# controller2.net
KiCad netlist of a schematic drawn in EAGLE
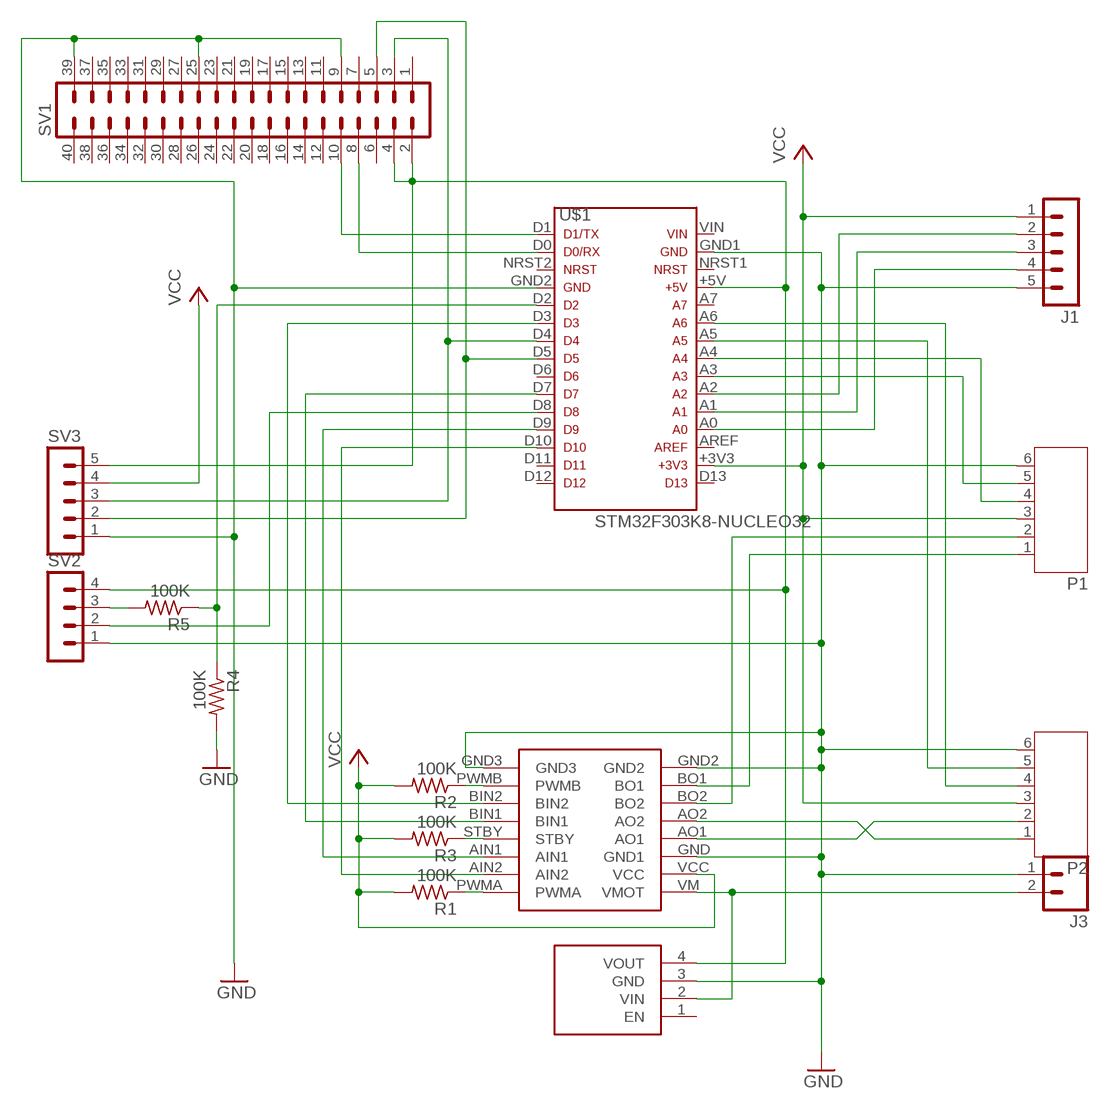
[diagram p0: schematic, sheet 1]

(export (version "E")
  (design (tool "Eeschema 10.0.6"))
  (components
    (comp (ref "J1")
      (value "MA05-1")
      (footprint "eagle-import:MA05-1")
      (libsource (lib "eagle-import") (part "MA05-1"))
    )
    (comp (ref "J3")
      (value "M02JST-PTH-VERT")
      (footprint "eagle-import:JST-2-PTH-VERT")
      (libsource (lib "eagle-import") (part "M02JST-PTH-VERT"))
    )
    (comp (ref "P1")
      (value "JST-PH6")
      (footprint "eagle-import:JST-PH6")
      (libsource (lib "eagle-import") (part "JST-PH6"))
    )
    (comp (ref "P2")
      (value "JST-PH6")
      (footprint "eagle-import:JST-PH6")
      (libsource (lib "eagle-import") (part "JST-PH6"))
    )
    (comp (ref "R1")
      (value "100K")
      (footprint "eagle-import:M0805")
      (libsource (lib "eagle-import") (part "R-US_M0805"))
    )
    (comp (ref "R2")
      (value "100K")
      (footprint "eagle-import:M0805")
      (libsource (lib "eagle-import") (part "R-US_M0805"))
    )
    (comp (ref "R3")
      (value "100K")
      (footprint "eagle-import:M0805")
      (libsource (lib "eagle-import") (part "R-US_M0805"))
    )
    (comp (ref "R4")
      (value "100K")
      (footprint "eagle-import:M0805")
      (libsource (lib "eagle-import") (part "R-US_M0805"))
    )
    (comp (ref "R5")
      (value "100K")
      (footprint "eagle-import:M0805")
      (libsource (lib "eagle-import") (part "R-US_M0805"))
    )
    (comp (ref "SV1")
      (value "MA20-2")
      (footprint "eagle-import:MA20-2")
      (libsource (lib "eagle-import") (part "MA20-2"))
    )
    (comp (ref "SV2")
      (value "MA04-1")
      (footprint "eagle-import:MA04-1")
      (libsource (lib "eagle-import") (part "MA04-1"))
    )
    (comp (ref "SV3")
      (value "MA05-1")
      (footprint "eagle-import:MA05-1")
      (libsource (lib "eagle-import") (part "MA05-1"))
    )
    (comp (ref "U$1")
      (value "STM32F303K8-NUCLEO32")
      (footprint "eagle-import:NUCLEO32")
      (libsource (lib "eagle-import") (part "STM32F303K8-NUCLEO32"))
    )
    (comp (ref "U$2")
      (value "TB6612FNG-CARRIER/SPARKFUN")
      (footprint "eagle-import:TB6612FNG-BRKOUT_SPARKFUN")
      (libsource (lib "eagle-import") (part "TB6612FNG-CARRIER/SPARKFUN"))
    )
    (comp (ref "U$3")
      (value "S7V8A")
      (footprint "eagle-import:S7V8")
      (libsource (lib "eagle-import") (part "S7V8A"))
    )
  )
  (nets
    (net (code "1") (name "GND") (class "Default")
      (node (ref "J1") (pin "5") (pinfunction "5_5") (pintype "passive"))
      (node (ref "J3") (pin "1") (pinfunction "1_1") (pintype "passive"))
      (node (ref "P1") (pin "6") (pinfunction "6_6") (pintype "passive"))
      (node (ref "P2") (pin "6") (pinfunction "6_6") (pintype "passive"))
      (node (ref "R4") (pin "2") (pinfunction "2_2") (pintype "passive"))
      (node (ref "SV1") (pin "25") (pinfunction "25_25") (pintype "passive"))
      (node (ref "SV1") (pin "39") (pinfunction "39_39") (pintype "passive"))
      (node (ref "SV1") (pin "9") (pinfunction "9_9") (pintype "passive"))
      (node (ref "SV2") (pin "1") (pinfunction "1_1") (pintype "passive"))
      (node (ref "SV3") (pin "1") (pinfunction "1_1") (pintype "passive"))
      (node (ref "U$1") (pin "GND1") (pinfunction "GND1_GND1") (pintype "passive"))
      (node (ref "U$1") (pin "GND2") (pinfunction "GND2_GND2") (pintype "passive"))
      (node (ref "U$2") (pin "GND") (pinfunction "GND1_GND") (pintype "bidirectional"))
      (node (ref "U$2") (pin "GND2") (pinfunction "GND2_GND2") (pintype "bidirectional"))
      (node (ref "U$2") (pin "GND3") (pinfunction "GND3_GND3") (pintype "bidirectional"))
      (node (ref "U$3") (pin "3") (pinfunction "GND_3") (pintype "bidirectional"))
    )
    (net (code "2") (name "Net-(J1-Pad2)") (class "Default")
      (node (ref "J1") (pin "2") (pinfunction "2_2") (pintype "passive"))
      (node (ref "U$1") (pin "A2") (pinfunction "A2_A2") (pintype "passive"))
    )
    (net (code "3") (name "Net-(J1-Pad3)") (class "Default")
      (node (ref "J1") (pin "3") (pinfunction "3_3") (pintype "passive"))
      (node (ref "U$1") (pin "A1") (pinfunction "A1_A1") (pintype "passive"))
    )
    (net (code "4") (name "Net-(J1-Pad4)") (class "Default")
      (node (ref "J1") (pin "4") (pinfunction "4_4") (pintype "passive"))
      (node (ref "U$1") (pin "A0") (pinfunction "A0_A0") (pintype "passive"))
    )
    (net (code "5") (name "Net-(P1-Pad1)") (class "Default")
      (node (ref "P1") (pin "1") (pinfunction "1_1") (pintype "passive"))
      (node (ref "U$2") (pin "BO1") (pinfunction "BO1_BO1") (pintype "bidirectional"))
    )
    (net (code "6") (name "Net-(P1-Pad2)") (class "Default")
      (node (ref "P1") (pin "2") (pinfunction "2_2") (pintype "passive"))
      (node (ref "U$2") (pin "BO2") (pinfunction "BO2_BO2") (pintype "bidirectional"))
    )
    (net (code "7") (name "Net-(P1-Pad4)") (class "Default")
      (node (ref "P1") (pin "4") (pinfunction "4_4") (pintype "passive"))
      (node (ref "U$1") (pin "A4") (pinfunction "A4_A4") (pintype "passive"))
    )
    (net (code "8") (name "Net-(P1-Pad5)") (class "Default")
      (node (ref "P1") (pin "5") (pinfunction "5_5") (pintype "passive"))
      (node (ref "U$1") (pin "A3") (pinfunction "A3_A3") (pintype "passive"))
    )
    (net (code "9") (name "Net-(P2-Pad1)") (class "Default")
      (node (ref "P2") (pin "1") (pinfunction "1_1") (pintype "passive"))
      (node (ref "U$2") (pin "AO2") (pinfunction "AO2_AO2") (pintype "bidirectional"))
    )
    (net (code "10") (name "Net-(P2-Pad2)") (class "Default")
      (node (ref "P2") (pin "2") (pinfunction "2_2") (pintype "passive"))
      (node (ref "U$2") (pin "AO1") (pinfunction "AO1_AO1") (pintype "bidirectional"))
    )
    (net (code "11") (name "Net-(P2-Pad4)") (class "Default")
      (node (ref "P2") (pin "4") (pinfunction "4_4") (pintype "passive"))
      (node (ref "U$1") (pin "A6") (pinfunction "A6_A6") (pintype "passive"))
    )
    (net (code "12") (name "Net-(P2-Pad5)") (class "Default")
      (node (ref "P2") (pin "5") (pinfunction "5_5") (pintype "passive"))
      (node (ref "U$1") (pin "A5") (pinfunction "A5_A5") (pintype "passive"))
    )
    (net (code "13") (name "Net-(R1-Pad1)") (class "Default")
      (node (ref "R1") (pin "1") (pinfunction "1_1") (pintype "passive"))
      (node (ref "U$2") (pin "PWMA") (pinfunction "PWMA_PWMA") (pintype "bidirectional"))
    )
    (net (code "14") (name "Net-(R2-Pad1)") (class "Default")
      (node (ref "R2") (pin "1") (pinfunction "1_1") (pintype "passive"))
      (node (ref "U$2") (pin "PWMB") (pinfunction "PWMB_PWMB") (pintype "bidirectional"))
    )
    (net (code "15") (name "Net-(R3-Pad1)") (class "Default")
      (node (ref "R3") (pin "1") (pinfunction "1_1") (pintype "passive"))
      (node (ref "U$2") (pin "STBY") (pinfunction "STBY_STBY") (pintype "bidirectional"))
    )
    (net (code "16") (name "Net-(R4-Pad1)") (class "Default")
      (node (ref "R4") (pin "1") (pinfunction "1_1") (pintype "passive"))
      (node (ref "R5") (pin "1") (pinfunction "1_1") (pintype "passive"))
      (node (ref "U$1") (pin "D2") (pinfunction "D2_D2") (pintype "passive"))
    )
    (net (code "17") (name "Net-(R5-Pad2)") (class "Default")
      (node (ref "R5") (pin "2") (pinfunction "2_2") (pintype "passive"))
      (node (ref "SV2") (pin "3") (pinfunction "3_3") (pintype "passive"))
    )
    (net (code "18") (name "Net-(SV1-Pad3)") (class "Default")
      (node (ref "SV1") (pin "3") (pinfunction "3_3") (pintype "passive"))
      (node (ref "SV3") (pin "3") (pinfunction "3_3") (pintype "passive"))
      (node (ref "U$1") (pin "D4") (pinfunction "D4_D4") (pintype "passive"))
    )
    (net (code "19") (name "Net-(SV1-Pad5)") (class "Default")
      (node (ref "SV1") (pin "5") (pinfunction "5_5") (pintype "passive"))
      (node (ref "SV3") (pin "2") (pinfunction "2_2") (pintype "passive"))
      (node (ref "U$1") (pin "D5") (pinfunction "D5_D5") (pintype "passive"))
    )
    (net (code "20") (name "Net-(SV1-Pad8)") (class "Default")
      (node (ref "SV1") (pin "8") (pinfunction "8_8") (pintype "passive"))
      (node (ref "U$1") (pin "D0") (pinfunction "D0_D0") (pintype "passive"))
    )
    (net (code "21") (name "Net-(SV1-Pad10)") (class "Default")
      (node (ref "SV1") (pin "10") (pinfunction "10_10") (pintype "passive"))
      (node (ref "U$1") (pin "D1") (pinfunction "D1_D1") (pintype "passive"))
    )
    (net (code "22") (name "Net-(SV2-Pad2)") (class "Default")
      (node (ref "SV2") (pin "2") (pinfunction "2_2") (pintype "passive"))
      (node (ref "U$1") (pin "D8") (pinfunction "D8_D8") (pintype "passive"))
    )
    (net (code "23") (name "Net-(U$1-PadD3)") (class "Default")
      (node (ref "U$1") (pin "D3") (pinfunction "D3_D3") (pintype "passive"))
      (node (ref "U$2") (pin "BIN2") (pinfunction "BIN2_BIN2") (pintype "bidirectional"))
    )
    (net (code "24") (name "Net-(U$1-PadD7)") (class "Default")
      (node (ref "U$1") (pin "D7") (pinfunction "D7_D7") (pintype "passive"))
      (node (ref "U$2") (pin "BIN1") (pinfunction "BIN1_BIN1") (pintype "bidirectional"))
    )
    (net (code "25") (name "Net-(U$1-PadD9)") (class "Default")
      (node (ref "U$1") (pin "D9") (pinfunction "D9_D9") (pintype "passive"))
      (node (ref "U$2") (pin "AIN1") (pinfunction "AIN1_AIN1") (pintype "bidirectional"))
    )
    (net (code "26") (name "Net-(U$1-PadD10)") (class "Default")
      (node (ref "U$1") (pin "D10") (pinfunction "D10_D10") (pintype "passive"))
      (node (ref "U$2") (pin "AIN2") (pinfunction "AIN2_AIN2") (pintype "bidirectional"))
    )
    (net (code "27") (name "Net-(U$2-VMOT)") (class "Default")
      (node (ref "J3") (pin "2") (pinfunction "2_2") (pintype "passive"))
      (node (ref "U$2") (pin "VM") (pinfunction "VMOT_VM") (pintype "bidirectional"))
      (node (ref "U$3") (pin "2") (pinfunction "VIN_2") (pintype "bidirectional"))
    )
    (net (code "28") (name "Net-(U$3-VOUT)") (class "Default")
      (node (ref "SV1") (pin "2") (pinfunction "2_2") (pintype "passive"))
      (node (ref "SV1") (pin "4") (pinfunction "4_4") (pintype "passive"))
      (node (ref "SV2") (pin "4") (pinfunction "4_4") (pintype "passive"))
      (node (ref "SV3") (pin "5") (pinfunction "5_5") (pintype "passive"))
      (node (ref "U$1") (pin "+5V") (pinfunction "+5V_+5V") (pintype "passive"))
      (node (ref "U$3") (pin "4") (pinfunction "VOUT_4") (pintype "bidirectional"))
    )
    (net (code "29") (name "VCC") (class "Default")
      (node (ref "J1") (pin "1") (pinfunction "1_1") (pintype "passive"))
      (node (ref "P1") (pin "3") (pinfunction "3_3") (pintype "passive"))
      (node (ref "P2") (pin "3") (pinfunction "3_3") (pintype "passive"))
      (node (ref "R1") (pin "2") (pinfunction "2_2") (pintype "passive"))
      (node (ref "R2") (pin "2") (pinfunction "2_2") (pintype "passive"))
      (node (ref "R3") (pin "2") (pinfunction "2_2") (pintype "passive"))
      (node (ref "SV3") (pin "4") (pinfunction "4_4") (pintype "passive"))
      (node (ref "U$1") (pin "+3V3") (pinfunction "+3V3_+3V3") (pintype "passive"))
      (node (ref "U$2") (pin "VCC") (pinfunction "VCC_VCC") (pintype "bidirectional"))
    )
    (net (code "30") (name "unconnected-(SV1-Pad1)") (class "Default")
      (node (ref "SV1") (pin "1") (pinfunction "1_1") (pintype "passive"))
    )
    (net (code "31") (name "unconnected-(SV1-Pad6)") (class "Default")
      (node (ref "SV1") (pin "6") (pinfunction "6_6") (pintype "passive"))
    )
    (net (code "32") (name "unconnected-(SV1-Pad7)") (class "Default")
      (node (ref "SV1") (pin "7") (pinfunction "7_7") (pintype "passive"))
    )
    (net (code "33") (name "unconnected-(SV1-Pad11)") (class "Default")
      (node (ref "SV1") (pin "11") (pinfunction "11_11") (pintype "passive"))
    )
    (net (code "34") (name "unconnected-(SV1-Pad12)") (class "Default")
      (node (ref "SV1") (pin "12") (pinfunction "12_12") (pintype "passive"))
    )
    (net (code "35") (name "unconnected-(SV1-Pad13)") (class "Default")
      (node (ref "SV1") (pin "13") (pinfunction "13_13") (pintype "passive"))
    )
    (net (code "36") (name "unconnected-(SV1-Pad14)") (class "Default")
      (node (ref "SV1") (pin "14") (pinfunction "14_14") (pintype "passive"))
    )
    (net (code "37") (name "unconnected-(SV1-Pad15)") (class "Default")
      (node (ref "SV1") (pin "15") (pinfunction "15_15") (pintype "passive"))
    )
    (net (code "38") (name "unconnected-(SV1-Pad16)") (class "Default")
      (node (ref "SV1") (pin "16") (pinfunction "16_16") (pintype "passive"))
    )
    (net (code "39") (name "unconnected-(SV1-Pad17)") (class "Default")
      (node (ref "SV1") (pin "17") (pinfunction "17_17") (pintype "passive"))
    )
    (net (code "40") (name "unconnected-(SV1-Pad18)") (class "Default")
      (node (ref "SV1") (pin "18") (pinfunction "18_18") (pintype "passive"))
    )
    (net (code "41") (name "unconnected-(SV1-Pad19)") (class "Default")
      (node (ref "SV1") (pin "19") (pinfunction "19_19") (pintype "passive"))
    )
    (net (code "42") (name "unconnected-(SV1-Pad20)") (class "Default")
      (node (ref "SV1") (pin "20") (pinfunction "20_20") (pintype "passive"))
    )
    (net (code "43") (name "unconnected-(SV1-Pad21)") (class "Default")
      (node (ref "SV1") (pin "21") (pinfunction "21_21") (pintype "passive"))
    )
    (net (code "44") (name "unconnected-(SV1-Pad22)") (class "Default")
      (node (ref "SV1") (pin "22") (pinfunction "22_22") (pintype "passive"))
    )
    (net (code "45") (name "unconnected-(SV1-Pad23)") (class "Default")
      (node (ref "SV1") (pin "23") (pinfunction "23_23") (pintype "passive"))
    )
    (net (code "46") (name "unconnected-(SV1-Pad24)") (class "Default")
      (node (ref "SV1") (pin "24") (pinfunction "24_24") (pintype "passive"))
    )
    (net (code "47") (name "unconnected-(SV1-Pad26)") (class "Default")
      (node (ref "SV1") (pin "26") (pinfunction "26_26") (pintype "passive"))
    )
    (net (code "48") (name "unconnected-(SV1-Pad27)") (class "Default")
      (node (ref "SV1") (pin "27") (pinfunction "27_27") (pintype "passive"))
    )
    (net (code "49") (name "unconnected-(SV1-Pad28)") (class "Default")
      (node (ref "SV1") (pin "28") (pinfunction "28_28") (pintype "passive"))
    )
    (net (code "50") (name "unconnected-(SV1-Pad29)") (class "Default")
      (node (ref "SV1") (pin "29") (pinfunction "29_29") (pintype "passive"))
    )
    (net (code "51") (name "unconnected-(SV1-Pad30)") (class "Default")
      (node (ref "SV1") (pin "30") (pinfunction "30_30") (pintype "passive"))
    )
    (net (code "52") (name "unconnected-(SV1-Pad31)") (class "Default")
      (node (ref "SV1") (pin "31") (pinfunction "31_31") (pintype "passive"))
    )
    (net (code "53") (name "unconnected-(SV1-Pad32)") (class "Default")
      (node (ref "SV1") (pin "32") (pinfunction "32_32") (pintype "passive"))
    )
    (net (code "54") (name "unconnected-(SV1-Pad33)") (class "Default")
      (node (ref "SV1") (pin "33") (pinfunction "33_33") (pintype "passive"))
    )
    (net (code "55") (name "unconnected-(SV1-Pad34)") (class "Default")
      (node (ref "SV1") (pin "34") (pinfunction "34_34") (pintype "passive"))
    )
    (net (code "56") (name "unconnected-(SV1-Pad35)") (class "Default")
      (node (ref "SV1") (pin "35") (pinfunction "35_35") (pintype "passive"))
    )
    (net (code "57") (name "unconnected-(SV1-Pad36)") (class "Default")
      (node (ref "SV1") (pin "36") (pinfunction "36_36") (pintype "passive"))
    )
    (net (code "58") (name "unconnected-(SV1-Pad37)") (class "Default")
      (node (ref "SV1") (pin "37") (pinfunction "37_37") (pintype "passive"))
    )
    (net (code "59") (name "unconnected-(SV1-Pad38)") (class "Default")
      (node (ref "SV1") (pin "38") (pinfunction "38_38") (pintype "passive"))
    )
    (net (code "60") (name "unconnected-(SV1-Pad40)") (class "Default")
      (node (ref "SV1") (pin "40") (pinfunction "40_40") (pintype "passive"))
    )
    (net (code "61") (name "unconnected-(U$1-PadA7)") (class "Default")
      (node (ref "U$1") (pin "A7") (pinfunction "A7_A7") (pintype "passive"))
    )
    (net (code "62") (name "unconnected-(U$1-PadAREF)") (class "Default")
      (node (ref "U$1") (pin "AREF") (pinfunction "AREF_AREF") (pintype "passive"))
    )
    (net (code "63") (name "unconnected-(U$1-PadD6)") (class "Default")
      (node (ref "U$1") (pin "D6") (pinfunction "D6_D6") (pintype "passive"))
    )
    (net (code "64") (name "unconnected-(U$1-PadD11)") (class "Default")
      (node (ref "U$1") (pin "D11") (pinfunction "D11_D11") (pintype "passive"))
    )
    (net (code "65") (name "unconnected-(U$1-PadD12)") (class "Default")
      (node (ref "U$1") (pin "D12") (pinfunction "D12_D12") (pintype "passive"))
    )
    (net (code "66") (name "unconnected-(U$1-PadD13)") (class "Default")
      (node (ref "U$1") (pin "D13") (pinfunction "D13_D13") (pintype "passive"))
    )
    (net (code "67") (name "unconnected-(U$1-PadNRST1)") (class "Default")
      (node (ref "U$1") (pin "NRST1") (pinfunction "NRST1_NRST1") (pintype "passive"))
    )
    (net (code "68") (name "unconnected-(U$1-PadNRST2)") (class "Default")
      (node (ref "U$1") (pin "NRST2") (pinfunction "NRST2_NRST2") (pintype "passive"))
    )
    (net (code "69") (name "unconnected-(U$1-PadVIN)") (class "Default")
      (node (ref "U$1") (pin "VIN") (pinfunction "VIN_VIN") (pintype "passive"))
    )
    (net (code "70") (name "unconnected-(U$3-EN-Pad1)") (class "Default")
      (node (ref "U$3") (pin "1") (pinfunction "EN_1") (pintype "bidirectional"))
    )
  )
)
